# SimpleFOCDriver.net
KiCad netlist of a schematic drawn in Altium Designer
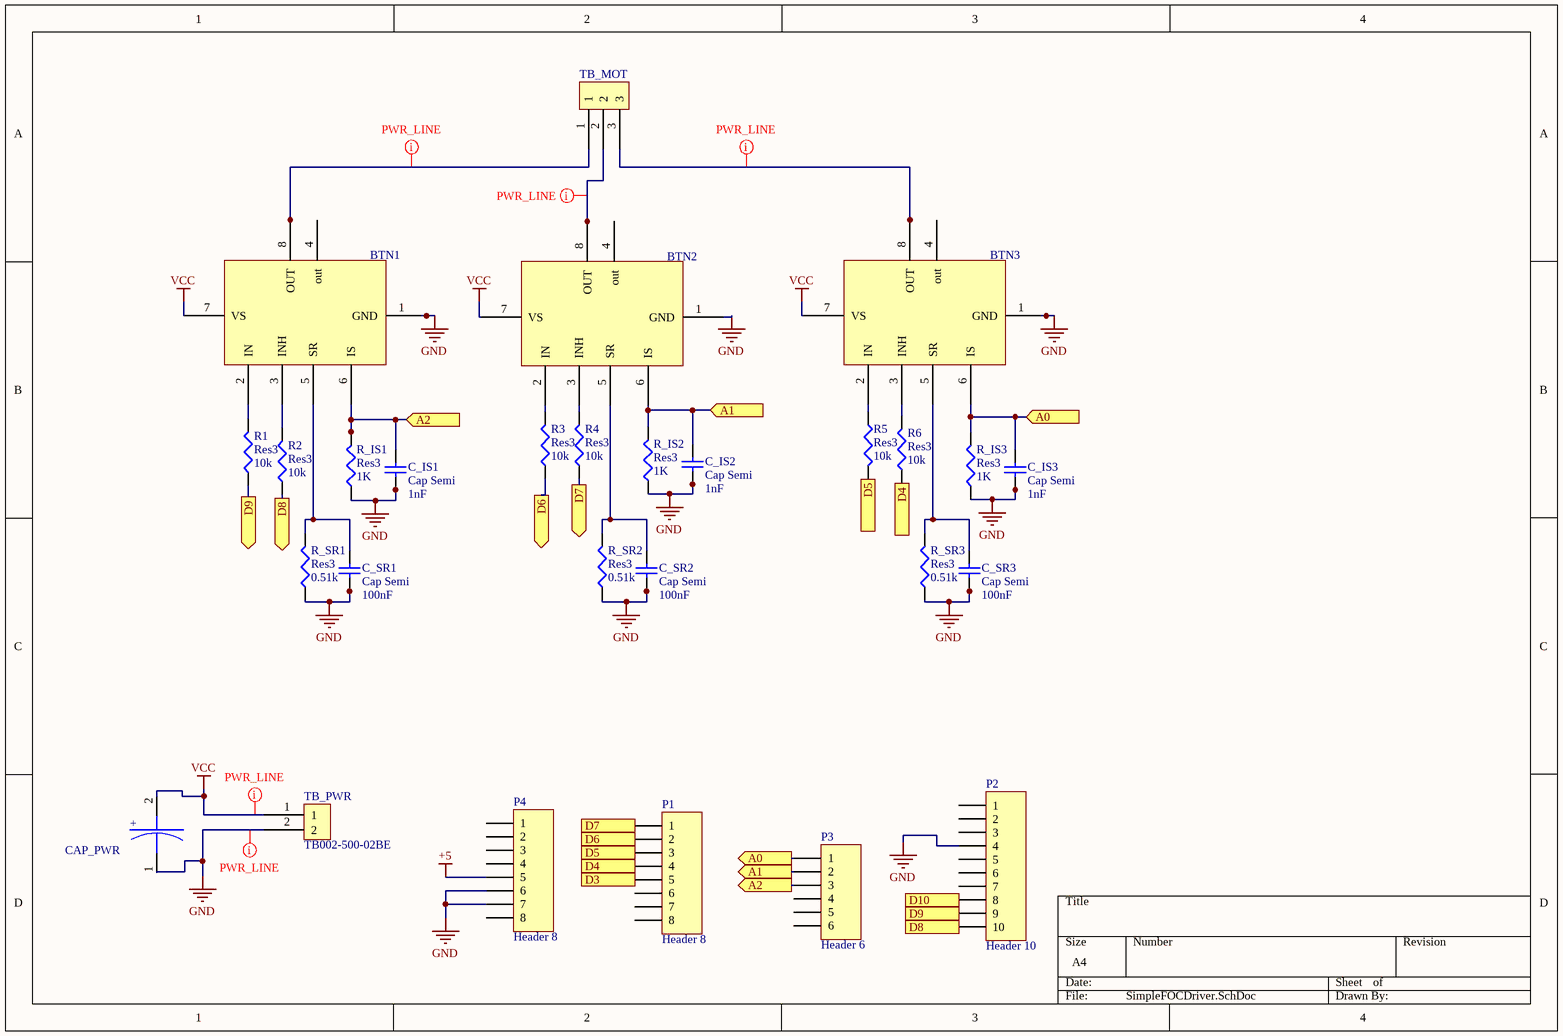
[diagram p0: SimpleFOCDriver.SchDoc]

(export (version "E")
  (design (tool "Eeschema 10.0.6"))
  (components
    (comp (ref "BTN1")
      (value "BTN8982")
      (footprint "BTN8982")
      (libsource (lib "ArduinoFOC") (part "BTN8982"))
    )
    (comp (ref "BTN2")
      (value "BTN8982")
      (footprint "BTN8982")
      (libsource (lib "ArduinoFOC") (part "BTN8982"))
    )
    (comp (ref "BTN3")
      (value "BTN8982")
      (footprint "BTN8982")
      (libsource (lib "ArduinoFOC") (part "BTN8982"))
    )
    (comp (ref "CAP_PWR")
      (value "VEJ471M1ETR1010")
      (footprint "VEJ471M1ETR1010")
      (libsource (lib "ArduinoFOC") (part "VEJ471M1ETR1010"))
    )
    (comp (ref "C_IS1")
      (value "Cap Semi")
      (footprint "1608[0603]")
      (description "Capacitor (Semiconductor SIM Model)")
      (fields (field (name "ALTIUM_VALUE") "1nF") (field (name "PUBLISHER") "Altium Limited"))
      (libsource (lib "Miscellaneous Devices") (part "Cap Semi"))
    )
    (comp (ref "C_IS2")
      (value "Cap Semi")
      (footprint "1608[0603]")
      (description "Capacitor (Semiconductor SIM Model)")
      (fields (field (name "ALTIUM_VALUE") "1nF") (field (name "PUBLISHER") "Altium Limited"))
      (libsource (lib "Miscellaneous Devices") (part "Cap Semi"))
    )
    (comp (ref "C_IS3")
      (value "Cap Semi")
      (footprint "1608[0603]")
      (description "Capacitor (Semiconductor SIM Model)")
      (fields (field (name "ALTIUM_VALUE") "1nF") (field (name "PUBLISHER") "Altium Limited"))
      (libsource (lib "Miscellaneous Devices") (part "Cap Semi"))
    )
    (comp (ref "C_SR1")
      (value "Cap Semi")
      (footprint "1608[0603]")
      (description "Capacitor (Semiconductor SIM Model)")
      (fields (field (name "ALTIUM_VALUE") "100nF") (field (name "PUBLISHER") "Altium Limited"))
      (libsource (lib "Miscellaneous Devices") (part "Cap Semi"))
    )
    (comp (ref "C_SR2")
      (value "Cap Semi")
      (footprint "1608[0603]")
      (description "Capacitor (Semiconductor SIM Model)")
      (fields (field (name "ALTIUM_VALUE") "100nF") (field (name "PUBLISHER") "Altium Limited"))
      (libsource (lib "Miscellaneous Devices") (part "Cap Semi"))
    )
    (comp (ref "C_SR3")
      (value "Cap Semi")
      (footprint "1608[0603]")
      (description "Capacitor (Semiconductor SIM Model)")
      (fields (field (name "ALTIUM_VALUE") "100nF") (field (name "PUBLISHER") "Altium Limited"))
      (libsource (lib "Miscellaneous Devices") (part "Cap Semi"))
    )
    (comp (ref "P1")
      (value "Header 8")
      (footprint "HDR1X8")
      (description "Header, 8-Pin")
      (fields (field (name "PUBLISHER") "Altium Limited"))
      (libsource (lib "Miscellaneous Connectors") (part "Header 8"))
    )
    (comp (ref "P2")
      (value "Header 10")
      (footprint "HDR1X10")
      (description "Header, 10-Pin")
      (fields (field (name "PUBLISHER") "Altium Limited"))
      (libsource (lib "Miscellaneous Connectors") (part "Header 10"))
    )
    (comp (ref "P3")
      (value "Header 6")
      (footprint "HDR1X6")
      (description "Header, 6-Pin")
      (fields (field (name "PUBLISHER") "Altium Limited"))
      (libsource (lib "Miscellaneous Connectors") (part "Header 6"))
    )
    (comp (ref "P4")
      (value "Header 8")
      (footprint "HDR1X8")
      (description "Header, 8-Pin")
      (fields (field (name "PUBLISHER") "Altium Limited"))
      (libsource (lib "Miscellaneous Connectors") (part "Header 8"))
    )
    (comp (ref "R1")
      (value "Res3")
      (footprint "J1-0603")
      (description "Resistor")
      (fields (field (name "ALTIUM_VALUE") "10k") (field (name "PUBLISHER") "Altium Limited"))
      (libsource (lib "Miscellaneous Devices") (part "Res3"))
    )
    (comp (ref "R2")
      (value "Res3")
      (footprint "J1-0603")
      (description "Resistor")
      (fields (field (name "ALTIUM_VALUE") "10k") (field (name "PUBLISHER") "Altium Limited"))
      (libsource (lib "Miscellaneous Devices") (part "Res3"))
    )
    (comp (ref "R3")
      (value "Res3")
      (footprint "J1-0603")
      (description "Resistor")
      (fields (field (name "ALTIUM_VALUE") "10k") (field (name "PUBLISHER") "Altium Limited"))
      (libsource (lib "Miscellaneous Devices") (part "Res3"))
    )
    (comp (ref "R4")
      (value "Res3")
      (footprint "J1-0603")
      (description "Resistor")
      (fields (field (name "ALTIUM_VALUE") "10k") (field (name "PUBLISHER") "Altium Limited"))
      (libsource (lib "Miscellaneous Devices") (part "Res3"))
    )
    (comp (ref "R5")
      (value "Res3")
      (footprint "J1-0603")
      (description "Resistor")
      (fields (field (name "ALTIUM_VALUE") "10k") (field (name "PUBLISHER") "Altium Limited"))
      (libsource (lib "Miscellaneous Devices") (part "Res3"))
    )
    (comp (ref "R6")
      (value "Res3")
      (footprint "J1-0603")
      (description "Resistor")
      (fields (field (name "ALTIUM_VALUE") "10k") (field (name "PUBLISHER") "Altium Limited"))
      (libsource (lib "Miscellaneous Devices") (part "Res3"))
    )
    (comp (ref "R_IS1")
      (value "Res3")
      (footprint "J1-0603")
      (description "Resistor")
      (fields (field (name "ALTIUM_VALUE") "1K") (field (name "PUBLISHER") "Altium Limited"))
      (libsource (lib "Miscellaneous Devices") (part "Res3"))
    )
    (comp (ref "R_IS2")
      (value "Res3")
      (footprint "J1-0603")
      (description "Resistor")
      (fields (field (name "ALTIUM_VALUE") "1K") (field (name "PUBLISHER") "Altium Limited"))
      (libsource (lib "Miscellaneous Devices") (part "Res3"))
    )
    (comp (ref "R_IS3")
      (value "Res3")
      (footprint "J1-0603")
      (description "Resistor")
      (fields (field (name "ALTIUM_VALUE") "1K") (field (name "PUBLISHER") "Altium Limited"))
      (libsource (lib "Miscellaneous Devices") (part "Res3"))
    )
    (comp (ref "R_SR1")
      (value "Res3")
      (footprint "J1-0603")
      (description "Resistor")
      (fields (field (name "ALTIUM_VALUE") "0.51k") (field (name "PUBLISHER") "Altium Limited"))
      (libsource (lib "Miscellaneous Devices") (part "Res3"))
    )
    (comp (ref "R_SR2")
      (value "Res3")
      (footprint "J1-0603")
      (description "Resistor")
      (fields (field (name "ALTIUM_VALUE") "0.51k") (field (name "PUBLISHER") "Altium Limited"))
      (libsource (lib "Miscellaneous Devices") (part "Res3"))
    )
    (comp (ref "R_SR3")
      (value "Res3")
      (footprint "J1-0603")
      (description "Resistor")
      (fields (field (name "ALTIUM_VALUE") "0.51k") (field (name "PUBLISHER") "Altium Limited"))
      (libsource (lib "Miscellaneous Devices") (part "Res3"))
    )
    (comp (ref "TB_MOT")
      (value "TB002-500-03BE")
      (footprint "TB002-500-03BE")
      (libsource (lib "ArduinoFOC") (part "TB002-500-03BE"))
    )
    (comp (ref "TB_PWR")
      (value "TB002-500-02BE")
      (footprint "TB002-500-02BE")
      (libsource (lib "ArduinoFOC") (part "TB002-500-02BE"))
    )
  )
  (nets
    (net (code "1") (name "+5") (class "Default")
      (node (ref "P4") (pin "5") (pinfunction "5_5") (pintype "passive"))
    )
    (net (code "2") (name "/A0") (class "Default")
      (node (ref "BTN3") (pin "6") (pinfunction "IS_6") (pintype "passive"))
      (node (ref "C_IS3") (pin "2") (pinfunction "2_2") (pintype "passive"))
      (node (ref "P3") (pin "1") (pinfunction "1_1") (pintype "passive"))
      (node (ref "R_IS3") (pin "2") (pinfunction "2_2") (pintype "passive"))
    )
    (net (code "3") (name "/A1") (class "Default")
      (node (ref "BTN2") (pin "6") (pinfunction "IS_6") (pintype "passive"))
      (node (ref "C_IS2") (pin "2") (pinfunction "2_2") (pintype "passive"))
      (node (ref "P3") (pin "2") (pinfunction "2_2") (pintype "passive"))
      (node (ref "R_IS2") (pin "2") (pinfunction "2_2") (pintype "passive"))
    )
    (net (code "4") (name "/A2") (class "Default")
      (node (ref "BTN1") (pin "6") (pinfunction "IS_6") (pintype "passive"))
      (node (ref "C_IS1") (pin "2") (pinfunction "2_2") (pintype "passive"))
      (node (ref "P3") (pin "3") (pinfunction "3_3") (pintype "passive"))
      (node (ref "R_IS1") (pin "2") (pinfunction "2_2") (pintype "passive"))
    )
    (net (code "5") (name "/D3") (class "Default")
      (node (ref "P1") (pin "5") (pinfunction "5_5") (pintype "passive"))
    )
    (net (code "6") (name "/D4") (class "Default")
      (node (ref "P1") (pin "4") (pinfunction "4_4") (pintype "passive"))
      (node (ref "R6") (pin "1") (pinfunction "1_1") (pintype "passive"))
    )
    (net (code "7") (name "/D5") (class "Default")
      (node (ref "P1") (pin "3") (pinfunction "3_3") (pintype "passive"))
      (node (ref "R5") (pin "2") (pinfunction "2_2") (pintype "passive"))
    )
    (net (code "8") (name "/D6") (class "Default")
      (node (ref "P1") (pin "2") (pinfunction "2_2") (pintype "passive"))
      (node (ref "R3") (pin "1") (pinfunction "1_1") (pintype "passive"))
    )
    (net (code "9") (name "/D7") (class "Default")
      (node (ref "P1") (pin "1") (pinfunction "1_1") (pintype "passive"))
      (node (ref "R4") (pin "1") (pinfunction "1_1") (pintype "passive"))
    )
    (net (code "10") (name "/D8") (class "Default")
      (node (ref "P2") (pin "10") (pinfunction "10_10") (pintype "passive"))
      (node (ref "R2") (pin "1") (pinfunction "1_1") (pintype "passive"))
    )
    (net (code "11") (name "/D9") (class "Default")
      (node (ref "P2") (pin "9") (pinfunction "9_9") (pintype "passive"))
      (node (ref "R1") (pin "1") (pinfunction "1_1") (pintype "passive"))
    )
    (net (code "12") (name "/D10") (class "Default")
      (node (ref "P2") (pin "8") (pinfunction "8_8") (pintype "passive"))
    )
    (net (code "13") (name "GND") (class "Default")
      (node (ref "BTN1") (pin "1") (pinfunction "GND_1") (pintype "passive"))
      (node (ref "BTN2") (pin "1") (pinfunction "GND_1") (pintype "passive"))
      (node (ref "BTN3") (pin "1") (pinfunction "GND_1") (pintype "passive"))
      (node (ref "CAP_PWR") (pin "1") (pinfunction "1_1") (pintype "passive"))
      (node (ref "C_IS1") (pin "1") (pinfunction "1_1") (pintype "passive"))
      (node (ref "C_IS2") (pin "1") (pinfunction "1_1") (pintype "passive"))
      (node (ref "C_IS3") (pin "1") (pinfunction "1_1") (pintype "passive"))
      (node (ref "C_SR1") (pin "1") (pinfunction "1_1") (pintype "passive"))
      (node (ref "C_SR2") (pin "1") (pinfunction "1_1") (pintype "passive"))
      (node (ref "C_SR3") (pin "1") (pinfunction "1_1") (pintype "passive"))
      (node (ref "P2") (pin "4") (pinfunction "4_4") (pintype "passive"))
      (node (ref "P4") (pin "6") (pinfunction "6_6") (pintype "passive"))
      (node (ref "P4") (pin "7") (pinfunction "7_7") (pintype "passive"))
      (node (ref "R_IS1") (pin "1") (pinfunction "1_1") (pintype "passive"))
      (node (ref "R_IS2") (pin "1") (pinfunction "1_1") (pintype "passive"))
      (node (ref "R_IS3") (pin "1") (pinfunction "1_1") (pintype "passive"))
      (node (ref "R_SR1") (pin "1") (pinfunction "1_1") (pintype "passive"))
      (node (ref "R_SR2") (pin "1") (pinfunction "1_1") (pintype "passive"))
      (node (ref "R_SR3") (pin "1") (pinfunction "1_1") (pintype "passive"))
      (node (ref "TB_PWR") (pin "2") (pinfunction "2_2") (pintype "passive"))
    )
    (net (code "14") (name "Net-(BTN1-IN)") (class "Default")
      (node (ref "BTN1") (pin "2") (pinfunction "IN_2") (pintype "passive"))
      (node (ref "R1") (pin "2") (pinfunction "2_2") (pintype "passive"))
    )
    (net (code "15") (name "Net-(BTN1-INH)") (class "Default")
      (node (ref "BTN1") (pin "3") (pinfunction "INH_3") (pintype "passive"))
      (node (ref "R2") (pin "2") (pinfunction "2_2") (pintype "passive"))
    )
    (net (code "16") (name "Net-(BTN1-OUT)") (class "Default")
      (node (ref "BTN1") (pin "8") (pinfunction "OUT_8") (pintype "passive"))
      (node (ref "TB_MOT") (pin "1") (pinfunction "1_1") (pintype "passive"))
    )
    (net (code "17") (name "Net-(BTN1-SR)") (class "Default")
      (node (ref "BTN1") (pin "5") (pinfunction "SR_5") (pintype "passive"))
      (node (ref "C_SR1") (pin "2") (pinfunction "2_2") (pintype "passive"))
      (node (ref "R_SR1") (pin "2") (pinfunction "2_2") (pintype "passive"))
    )
    (net (code "18") (name "Net-(BTN2-IN)") (class "Default")
      (node (ref "BTN2") (pin "2") (pinfunction "IN_2") (pintype "passive"))
      (node (ref "R3") (pin "2") (pinfunction "2_2") (pintype "passive"))
    )
    (net (code "19") (name "Net-(BTN2-INH)") (class "Default")
      (node (ref "BTN2") (pin "3") (pinfunction "INH_3") (pintype "passive"))
      (node (ref "R4") (pin "2") (pinfunction "2_2") (pintype "passive"))
    )
    (net (code "20") (name "Net-(BTN2-OUT)") (class "Default")
      (node (ref "BTN2") (pin "8") (pinfunction "OUT_8") (pintype "passive"))
      (node (ref "TB_MOT") (pin "2") (pinfunction "2_2") (pintype "passive"))
    )
    (net (code "21") (name "Net-(BTN2-SR)") (class "Default")
      (node (ref "BTN2") (pin "5") (pinfunction "SR_5") (pintype "passive"))
      (node (ref "C_SR2") (pin "2") (pinfunction "2_2") (pintype "passive"))
      (node (ref "R_SR2") (pin "2") (pinfunction "2_2") (pintype "passive"))
    )
    (net (code "22") (name "Net-(BTN3-IN)") (class "Default")
      (node (ref "BTN3") (pin "2") (pinfunction "IN_2") (pintype "passive"))
      (node (ref "R5") (pin "1") (pinfunction "1_1") (pintype "passive"))
    )
    (net (code "23") (name "Net-(BTN3-INH)") (class "Default")
      (node (ref "BTN3") (pin "3") (pinfunction "INH_3") (pintype "passive"))
      (node (ref "R6") (pin "2") (pinfunction "2_2") (pintype "passive"))
    )
    (net (code "24") (name "Net-(BTN3-OUT)") (class "Default")
      (node (ref "BTN3") (pin "8") (pinfunction "OUT_8") (pintype "passive"))
      (node (ref "TB_MOT") (pin "3") (pinfunction "3_3") (pintype "passive"))
    )
    (net (code "25") (name "Net-(BTN3-SR)") (class "Default")
      (node (ref "BTN3") (pin "5") (pinfunction "SR_5") (pintype "passive"))
      (node (ref "C_SR3") (pin "2") (pinfunction "2_2") (pintype "passive"))
      (node (ref "R_SR3") (pin "2") (pinfunction "2_2") (pintype "passive"))
    )
    (net (code "26") (name "VCC") (class "Default")
      (node (ref "BTN1") (pin "7") (pinfunction "VS_7") (pintype "passive"))
      (node (ref "BTN2") (pin "7") (pinfunction "VS_7") (pintype "passive"))
      (node (ref "BTN3") (pin "7") (pinfunction "VS_7") (pintype "passive"))
      (node (ref "CAP_PWR") (pin "2") (pinfunction "+_2") (pintype "passive"))
      (node (ref "TB_PWR") (pin "1") (pinfunction "1_1") (pintype "passive"))
    )
    (net (code "27") (name "unconnected-(BTN1-out-Pad4)") (class "Default")
      (node (ref "BTN1") (pin "4") (pinfunction "out_4") (pintype "passive"))
    )
    (net (code "28") (name "unconnected-(BTN2-out-Pad4)") (class "Default")
      (node (ref "BTN2") (pin "4") (pinfunction "out_4") (pintype "passive"))
    )
    (net (code "29") (name "unconnected-(BTN3-out-Pad4)") (class "Default")
      (node (ref "BTN3") (pin "4") (pinfunction "out_4") (pintype "passive"))
    )
    (net (code "30") (name "unconnected-(P1-Pad6)") (class "Default")
      (node (ref "P1") (pin "6") (pinfunction "6_6") (pintype "passive"))
    )
    (net (code "31") (name "unconnected-(P1-Pad7)") (class "Default")
      (node (ref "P1") (pin "7") (pinfunction "7_7") (pintype "passive"))
    )
    (net (code "32") (name "unconnected-(P1-Pad8)") (class "Default")
      (node (ref "P1") (pin "8") (pinfunction "8_8") (pintype "passive"))
    )
    (net (code "33") (name "unconnected-(P2-Pad1)") (class "Default")
      (node (ref "P2") (pin "1") (pinfunction "1_1") (pintype "passive"))
    )
    (net (code "34") (name "unconnected-(P2-Pad2)") (class "Default")
      (node (ref "P2") (pin "2") (pinfunction "2_2") (pintype "passive"))
    )
    (net (code "35") (name "unconnected-(P2-Pad3)") (class "Default")
      (node (ref "P2") (pin "3") (pinfunction "3_3") (pintype "passive"))
    )
    (net (code "36") (name "unconnected-(P2-Pad5)") (class "Default")
      (node (ref "P2") (pin "5") (pinfunction "5_5") (pintype "passive"))
    )
    (net (code "37") (name "unconnected-(P2-Pad6)") (class "Default")
      (node (ref "P2") (pin "6") (pinfunction "6_6") (pintype "passive"))
    )
    (net (code "38") (name "unconnected-(P2-Pad7)") (class "Default")
      (node (ref "P2") (pin "7") (pinfunction "7_7") (pintype "passive"))
    )
    (net (code "39") (name "unconnected-(P3-Pad4)") (class "Default")
      (node (ref "P3") (pin "4") (pinfunction "4_4") (pintype "passive"))
    )
    (net (code "40") (name "unconnected-(P3-Pad5)") (class "Default")
      (node (ref "P3") (pin "5") (pinfunction "5_5") (pintype "passive"))
    )
    (net (code "41") (name "unconnected-(P3-Pad6)") (class "Default")
      (node (ref "P3") (pin "6") (pinfunction "6_6") (pintype "passive"))
    )
    (net (code "42") (name "unconnected-(P4-Pad1)") (class "Default")
      (node (ref "P4") (pin "1") (pinfunction "1_1") (pintype "passive"))
    )
    (net (code "43") (name "unconnected-(P4-Pad2)") (class "Default")
      (node (ref "P4") (pin "2") (pinfunction "2_2") (pintype "passive"))
    )
    (net (code "44") (name "unconnected-(P4-Pad3)") (class "Default")
      (node (ref "P4") (pin "3") (pinfunction "3_3") (pintype "passive"))
    )
    (net (code "45") (name "unconnected-(P4-Pad4)") (class "Default")
      (node (ref "P4") (pin "4") (pinfunction "4_4") (pintype "passive"))
    )
    (net (code "46") (name "unconnected-(P4-Pad8)") (class "Default")
      (node (ref "P4") (pin "8") (pinfunction "8_8") (pintype "passive"))
    )
  )
)
